# Capacitive_Moisture_Sensor.net
KiCad netlist of a schematic drawn in EAGLE
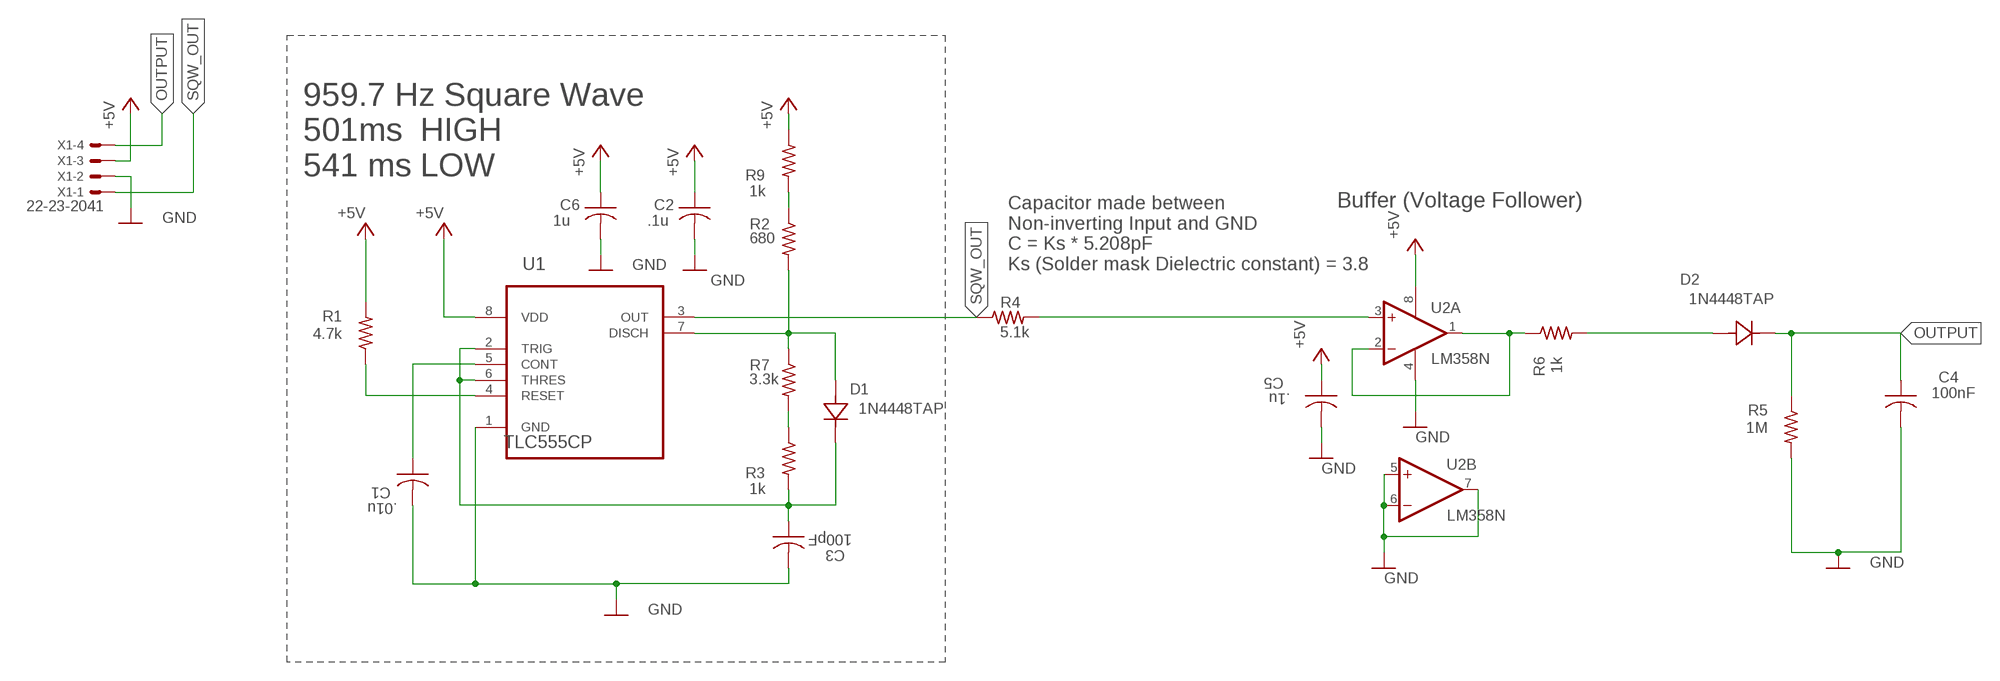
[diagram p0: schematic, sheet 1]

(export (version "E")
  (design (tool "Eeschema 10.0.6"))
  (components
    (comp (ref "C1")
      (value ".01u")
      (footprint "eagle-import:C1206")
      (libsource (lib "eagle-import") (part "C-USC1206"))
    )
    (comp (ref "C2")
      (value ".1u")
      (footprint "eagle-import:C1206")
      (libsource (lib "eagle-import") (part "C-USC1206"))
    )
    (comp (ref "C3")
      (value "100pF")
      (footprint "eagle-import:C1206")
      (libsource (lib "eagle-import") (part "C-USC1206"))
    )
    (comp (ref "C4")
      (value "100nF")
      (footprint "eagle-import:C1206")
      (libsource (lib "eagle-import") (part "C-USC1206"))
    )
    (comp (ref "C5")
      (value ".1u")
      (footprint "eagle-import:C1206")
      (libsource (lib "eagle-import") (part "C-USC1206"))
    )
    (comp (ref "C6")
      (value "1u")
      (footprint "eagle-import:C1206")
      (libsource (lib "eagle-import") (part "C-USC1206"))
    )
    (comp (ref "D1")
      (value "1N4448TAP")
      (footprint "eagle-import:DO-35")
      (libsource (lib "eagle-import") (part "1N4448TAP"))
    )
    (comp (ref "D2")
      (value "1N4448TAP")
      (footprint "eagle-import:DO-35")
      (libsource (lib "eagle-import") (part "1N4448TAP"))
    )
    (comp (ref "R1")
      (value "4.7k")
      (footprint "eagle-import:R1206")
      (libsource (lib "eagle-import") (part "R-US_R1206"))
    )
    (comp (ref "R2")
      (value "680")
      (footprint "eagle-import:R1206")
      (libsource (lib "eagle-import") (part "R-US_R1206"))
    )
    (comp (ref "R3")
      (value "1k")
      (footprint "eagle-import:R1206")
      (libsource (lib "eagle-import") (part "R-US_R1206"))
    )
    (comp (ref "R4")
      (value "5.1k")
      (footprint "eagle-import:R1206")
      (libsource (lib "eagle-import") (part "R-US_R1206"))
    )
    (comp (ref "R5")
      (value "1M")
      (footprint "eagle-import:R1206")
      (libsource (lib "eagle-import") (part "R-US_R1206"))
    )
    (comp (ref "R6")
      (value "1k")
      (footprint "eagle-import:R1206")
      (libsource (lib "eagle-import") (part "R-US_R1206"))
    )
    (comp (ref "R7")
      (value "3.3k")
      (footprint "eagle-import:R1206")
      (libsource (lib "eagle-import") (part "R-US_R1206"))
    )
    (comp (ref "R9")
      (value "1k")
      (footprint "eagle-import:R1206")
      (libsource (lib "eagle-import") (part "R-US_R1206"))
    )
    (comp (ref "U1")
      (value "TLC555CP")
      (footprint "eagle-import:DIP254P762X508-8")
      (fields (field (name "MF") "Texas Instruments"))
      (libsource (lib "eagle-import") (part "TLC555CP"))
    )
    (comp (ref "U2")
      (value "LM358N")
      (footprint "eagle-import:DIL08")
      (libsource (lib "eagle-import") (part "LM358N"))
    )
    (comp (ref "X1")
      (value "22-23-2041")
      (footprint "eagle-import:22-23-2041")
      (fields (field (name "MF") "MOLEX"))
      (libsource (lib "eagle-import") (part "22-23-2041"))
    )
  )
  (nets
    (net (code "1") (name "+5V") (class "Default")
      (node (ref "C2") (pin "1") (pinfunction "1_1") (pintype "passive"))
      (node (ref "C5") (pin "1") (pinfunction "1_1") (pintype "passive"))
      (node (ref "C6") (pin "1") (pinfunction "1_1") (pintype "passive"))
      (node (ref "R1") (pin "2") (pinfunction "2_2") (pintype "passive"))
      (node (ref "R9") (pin "1") (pinfunction "1_1") (pintype "passive"))
      (node (ref "U1") (pin "8") (pinfunction "VDD_8") (pintype "power_in"))
      (node (ref "U2") (pin "8") (pinfunction "V+_8") (pintype "power_in"))
      (node (ref "X1") (pin "3") (pinfunction "S_3") (pintype "passive"))
    )
    (net (code "2") (name "GND") (class "Default")
      (node (ref "C1") (pin "2") (pinfunction "2_2") (pintype "passive"))
      (node (ref "C2") (pin "2") (pinfunction "2_2") (pintype "passive"))
      (node (ref "C3") (pin "2") (pinfunction "2_2") (pintype "passive"))
      (node (ref "C4") (pin "2") (pinfunction "2_2") (pintype "passive"))
      (node (ref "C5") (pin "2") (pinfunction "2_2") (pintype "passive"))
      (node (ref "C6") (pin "2") (pinfunction "2_2") (pintype "passive"))
      (node (ref "R5") (pin "2") (pinfunction "2_2") (pintype "passive"))
      (node (ref "U1") (pin "1") (pinfunction "GND_1") (pintype "passive"))
      (node (ref "U2") (pin "4") (pinfunction "V-_4") (pintype "power_in"))
      (node (ref "U2") (pin "5") (pinfunction "+IN_5") (pintype "input"))
      (node (ref "U2") (pin "6") (pinfunction "-IN_6") (pintype "input"))
      (node (ref "U2") (pin "7") (pinfunction "OUT_7") (pintype "output"))
      (node (ref "X1") (pin "2") (pinfunction "S_2") (pintype "passive"))
    )
    (net (code "3") (name "Net-(D2-Pad2)") (class "Default")
      (node (ref "D2") (pin "2") (pinfunction "2_2") (pintype "passive"))
      (node (ref "R6") (pin "2") (pinfunction "2_2") (pintype "passive"))
    )
    (net (code "4") (name "Net-(R2-Pad1)") (class "Default")
      (node (ref "R2") (pin "1") (pinfunction "1_1") (pintype "passive"))
      (node (ref "R9") (pin "2") (pinfunction "2_2") (pintype "passive"))
    )
    (net (code "5") (name "Net-(R3-Pad1)") (class "Default")
      (node (ref "R3") (pin "1") (pinfunction "1_1") (pintype "passive"))
      (node (ref "R7") (pin "2") (pinfunction "2_2") (pintype "passive"))
    )
    (net (code "6") (name "Net-(U1-CONT)") (class "Default")
      (node (ref "C1") (pin "1") (pinfunction "1_1") (pintype "passive"))
      (node (ref "U1") (pin "5") (pinfunction "CONT_5") (pintype "input"))
    )
    (net (code "7") (name "Net-(U1-DISCH)") (class "Default")
      (node (ref "D1") (pin "2") (pinfunction "2_2") (pintype "passive"))
      (node (ref "R2") (pin "2") (pinfunction "2_2") (pintype "passive"))
      (node (ref "R7") (pin "1") (pinfunction "1_1") (pintype "passive"))
      (node (ref "U1") (pin "7") (pinfunction "DISCH_7") (pintype "output"))
    )
    (net (code "8") (name "Net-(U1-RESET)") (class "Default")
      (node (ref "R1") (pin "1") (pinfunction "1_1") (pintype "passive"))
      (node (ref "U1") (pin "4") (pinfunction "RESET_4") (pintype "input"))
    )
    (net (code "9") (name "Net-(U1-THRES)") (class "Default")
      (node (ref "C3") (pin "1") (pinfunction "1_1") (pintype "passive"))
      (node (ref "D1") (pin "1") (pinfunction "1_1") (pintype "passive"))
      (node (ref "R3") (pin "2") (pinfunction "2_2") (pintype "passive"))
      (node (ref "U1") (pin "2") (pinfunction "TRIG_2") (pintype "input"))
      (node (ref "U1") (pin "6") (pinfunction "THRES_6") (pintype "input"))
    )
    (net (code "10") (name "Net-(U2A-+IN)") (class "Default")
      (node (ref "R4") (pin "2") (pinfunction "2_2") (pintype "passive"))
      (node (ref "U2") (pin "3") (pinfunction "+IN_3") (pintype "input"))
    )
    (net (code "11") (name "Net-(U2A--IN)") (class "Default")
      (node (ref "R6") (pin "1") (pinfunction "1_1") (pintype "passive"))
      (node (ref "U2") (pin "1") (pinfunction "OUT_1") (pintype "output"))
      (node (ref "U2") (pin "2") (pinfunction "-IN_2") (pintype "input"))
    )
    (net (code "12") (name "OUTPUT") (class "Default")
      (node (ref "C4") (pin "1") (pinfunction "1_1") (pintype "passive"))
      (node (ref "D2") (pin "1") (pinfunction "1_1") (pintype "passive"))
      (node (ref "R5") (pin "1") (pinfunction "1_1") (pintype "passive"))
      (node (ref "X1") (pin "4") (pinfunction "S_4") (pintype "passive"))
    )
    (net (code "13") (name "SQW_OUT") (class "Default")
      (node (ref "R4") (pin "1") (pinfunction "1_1") (pintype "passive"))
      (node (ref "U1") (pin "3") (pinfunction "OUT_3") (pintype "output"))
      (node (ref "X1") (pin "1") (pinfunction "S_1") (pintype "passive"))
    )
  )
)
